# LED.net
KiCad netlist of a schematic drawn in Altium Designer
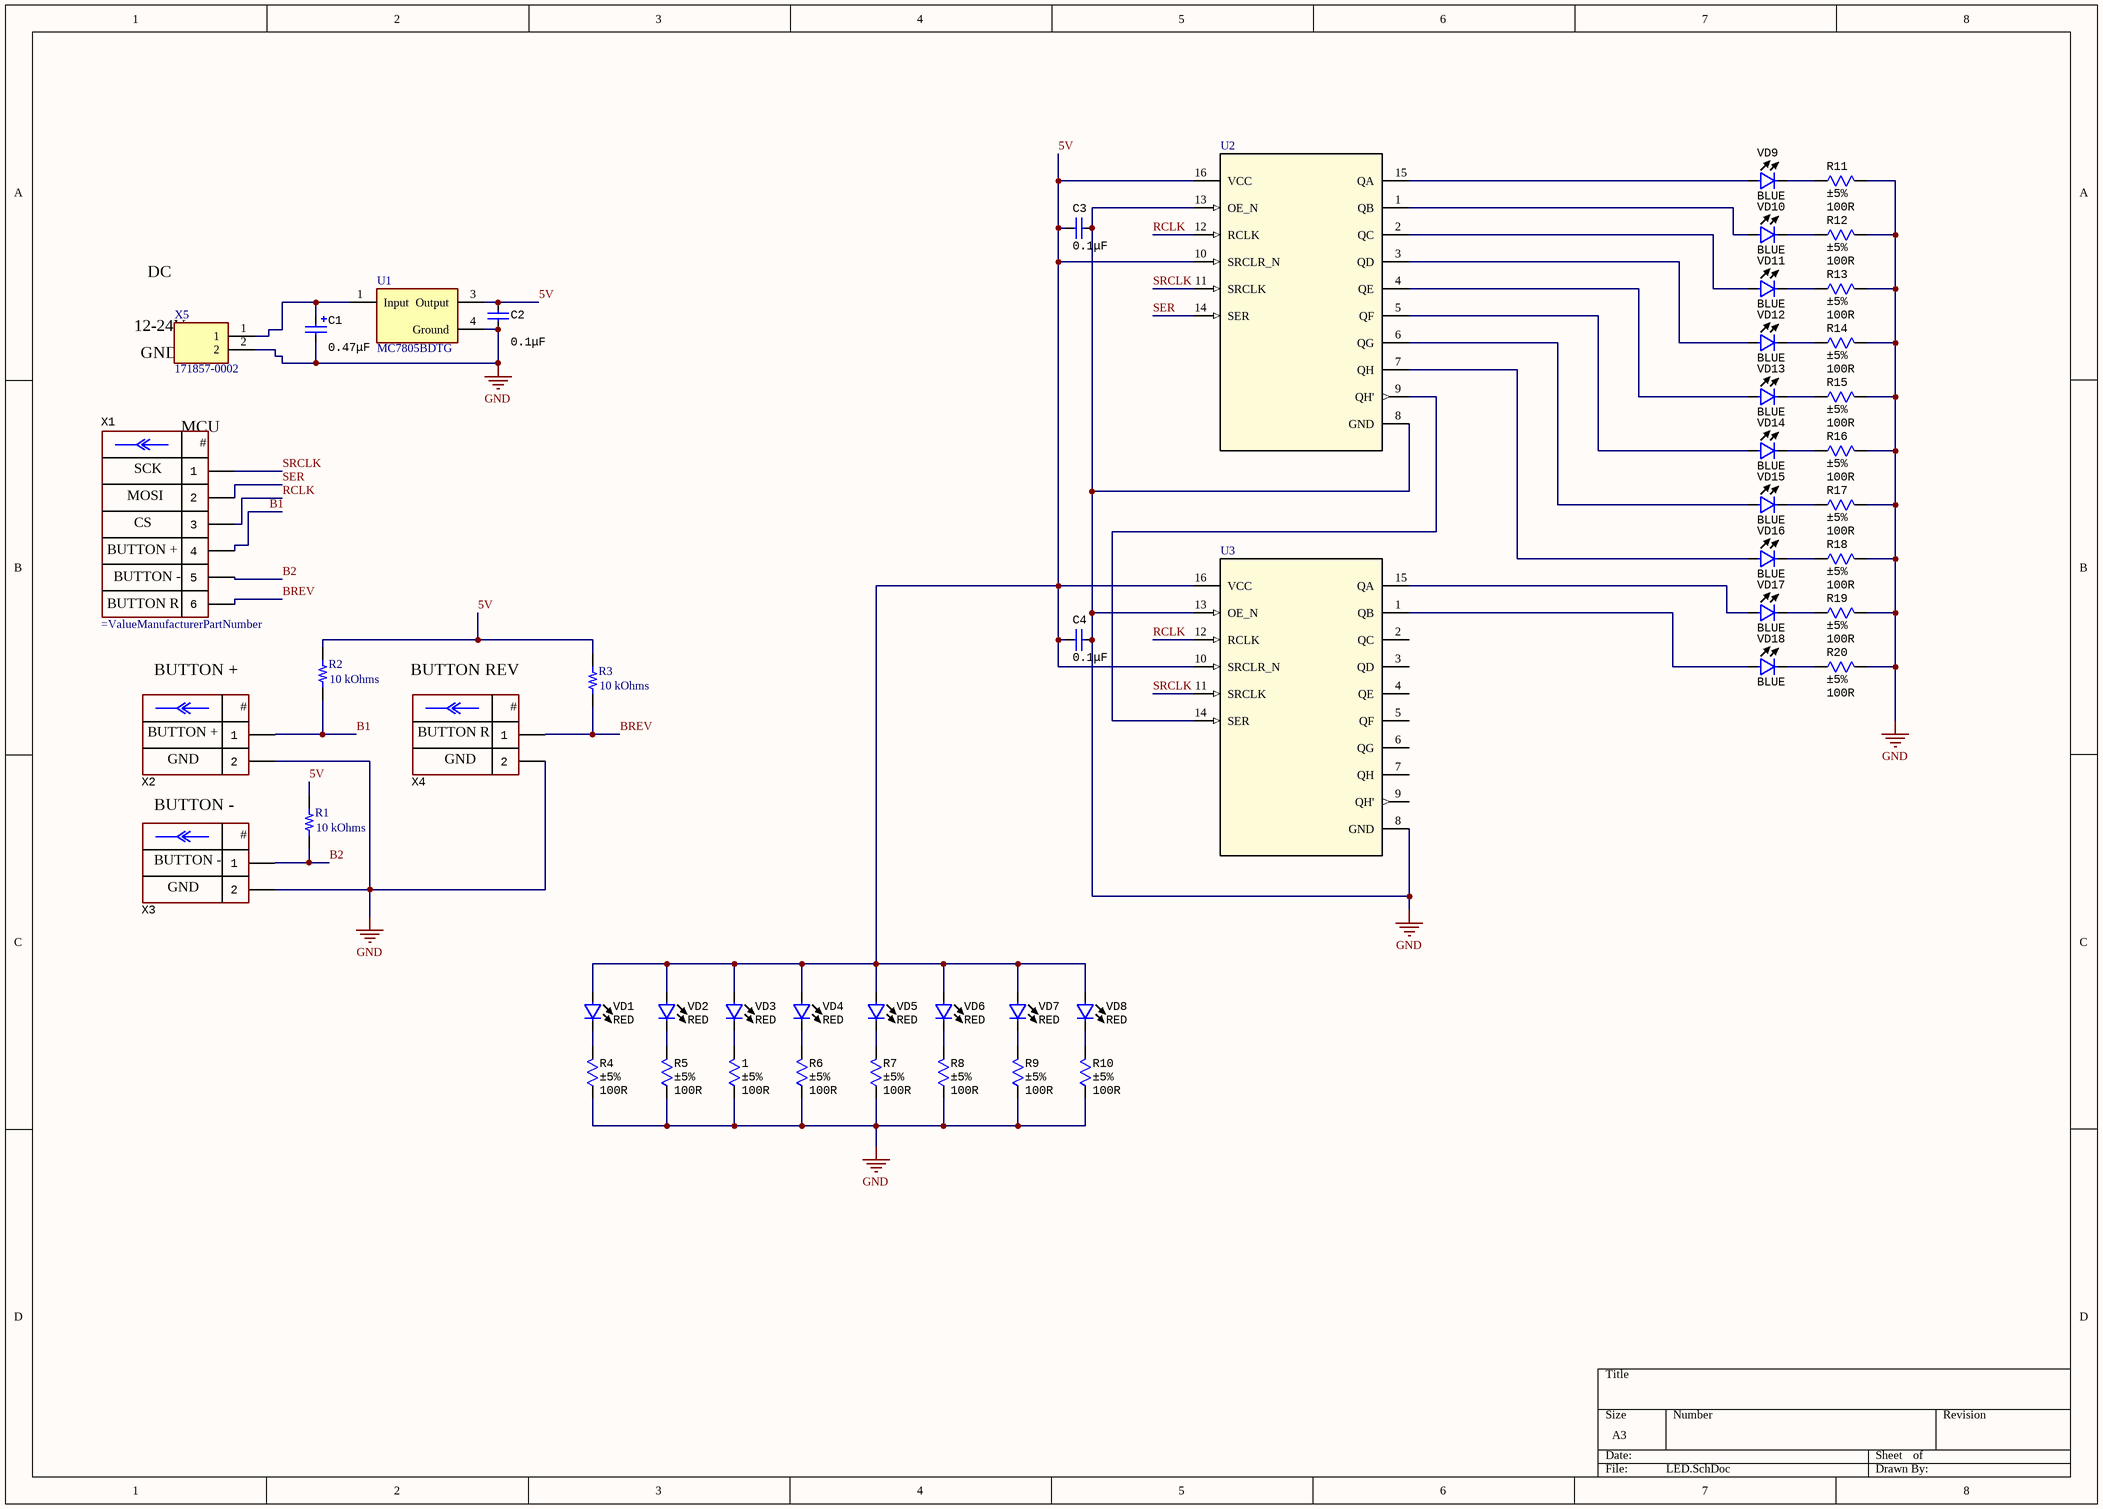
[diagram p0: LED.SchDoc]

(export (version "E")
  (design (tool "Eeschema 10.0.6"))
  (components
    (comp (ref "1")
      (value "100R")
      (footprint "standard-case:RES: 0805")
      (fields
        (field (name "MANUFACTURER") "Yageo")
        (field (name "PARTNUMBER") "RC0201JR-07100RL")
        (field (name "VALUEMANUFACTURERPARTNUMBER") "Resistor film, 100R, ±5%, 0201, 0.05W, -55...+125°C")
        (field (name "TOLERANCE") "±5%")
      )
      (libsource (lib "resistor") (part "Resistor"))
    )
    (comp (ref "C1")
      (value "0.47μF")
      (footprint "standard-case:CAP: TANTAL-A")
      (fields
        (field (name "MANUFACTURER") "AVX")
        (field (name "PARTNUMBER") "F930J107KAAAJ6")
        (field (name "VALUEMANUFACTURERPARTNUMBER") "Tantalum capacitor, 0.47μF, 6.3V, ±10%, 2Ohm, case A (3216), -55...+125°C")
      )
      (libsource (lib "capacitor") (part "Tantal"))
    )
    (comp (ref "C2")
      (value "0.1μF")
      (footprint "standard-case:CAP: 0805")
      (fields
        (field (name "MANUFACTURER") "Yageo")
        (field (name "PARTNUMBER") "CC0201KRX7R7BB103")
        (field (name "VALUEMANUFACTURERPARTNUMBER") "Ceramic capacitor, 0.1μF, X7R, ±10%, 16V, 0201, -55...+125°C")
      )
      (libsource (lib "capacitor") (part "Ceramic"))
    )
    (comp (ref "C3")
      (value "0.1μF")
      (footprint "standard-case:CAP: 0805")
      (fields
        (field (name "MANUFACTURER") "Yageo")
        (field (name "PARTNUMBER") "CC0201KRX7R7BB103")
        (field (name "VALUEMANUFACTURERPARTNUMBER") "Ceramic capacitor, 0.1μF, X7R, ±10%, 16V, 0201, -55...+125°C")
      )
      (libsource (lib "capacitor") (part "Ceramic"))
    )
    (comp (ref "C4")
      (value "0.1μF")
      (footprint "standard-case:CAP: 0805")
      (fields
        (field (name "MANUFACTURER") "Yageo")
        (field (name "PARTNUMBER") "CC0201KRX7R7BB103")
        (field (name "VALUEMANUFACTURERPARTNUMBER") "Ceramic capacitor, 0.1μF, X7R, ±10%, 16V, 0201, -55...+125°C")
      )
      (libsource (lib "capacitor") (part "Ceramic"))
    )
    (comp (ref "R1")
      (value "10 kOhms")
      (footprint "RES 0805_2012")
      (description "RES SMD 10K OHM 0.5% 1/8W 0805")
      (fields (field (name "PART NUMBER") "RT0805DRD0710KL") (field (name "MANUFACTURER") "Yageo"))
      (libsource (lib "Celestial Altium Library - altium_library") (part "Resistor"))
    )
    (comp (ref "R2")
      (value "10 kOhms")
      (footprint "RES 0805_2012")
      (description "RES SMD 10K OHM 0.5% 1/8W 0805")
      (fields (field (name "PART NUMBER") "RT0805DRD0710KL") (field (name "MANUFACTURER") "Yageo"))
      (libsource (lib "Celestial Altium Library - altium_library") (part "Resistor"))
    )
    (comp (ref "R3")
      (value "10 kOhms")
      (footprint "RES 0805_2012")
      (description "RES SMD 10K OHM 0.5% 1/8W 0805")
      (fields (field (name "PART NUMBER") "RT0805DRD0710KL") (field (name "MANUFACTURER") "Yageo"))
      (libsource (lib "Celestial Altium Library - altium_library") (part "Resistor"))
    )
    (comp (ref "R4")
      (value "100R")
      (footprint "standard-case:RES: 0805")
      (fields
        (field (name "MANUFACTURER") "Yageo")
        (field (name "PARTNUMBER") "RC0201JR-07100RL")
        (field (name "VALUEMANUFACTURERPARTNUMBER") "Resistor film, 100R, ±5%, 0201, 0.05W, -55...+125°C")
        (field (name "TOLERANCE") "±5%")
      )
      (libsource (lib "resistor") (part "Resistor"))
    )
    (comp (ref "R5")
      (value "100R")
      (footprint "standard-case:RES: 0805")
      (fields
        (field (name "MANUFACTURER") "Yageo")
        (field (name "PARTNUMBER") "RC0201JR-07100RL")
        (field (name "VALUEMANUFACTURERPARTNUMBER") "Resistor film, 100R, ±5%, 0201, 0.05W, -55...+125°C")
        (field (name "TOLERANCE") "±5%")
      )
      (libsource (lib "resistor") (part "Resistor"))
    )
    (comp (ref "R6")
      (value "100R")
      (footprint "standard-case:RES: 0805")
      (fields
        (field (name "MANUFACTURER") "Yageo")
        (field (name "PARTNUMBER") "RC0201JR-07100RL")
        (field (name "VALUEMANUFACTURERPARTNUMBER") "Resistor film, 100R, ±5%, 0201, 0.05W, -55...+125°C")
        (field (name "TOLERANCE") "±5%")
      )
      (libsource (lib "resistor") (part "Resistor"))
    )
    (comp (ref "R7")
      (value "100R")
      (footprint "standard-case:RES: 0805")
      (fields
        (field (name "MANUFACTURER") "Yageo")
        (field (name "PARTNUMBER") "RC0201JR-07100RL")
        (field (name "VALUEMANUFACTURERPARTNUMBER") "Resistor film, 100R, ±5%, 0201, 0.05W, -55...+125°C")
        (field (name "TOLERANCE") "±5%")
      )
      (libsource (lib "resistor") (part "Resistor"))
    )
    (comp (ref "R8")
      (value "100R")
      (footprint "standard-case:RES: 0805")
      (fields
        (field (name "MANUFACTURER") "Yageo")
        (field (name "PARTNUMBER") "RC0201JR-07100RL")
        (field (name "VALUEMANUFACTURERPARTNUMBER") "Resistor film, 100R, ±5%, 0201, 0.05W, -55...+125°C")
        (field (name "TOLERANCE") "±5%")
      )
      (libsource (lib "resistor") (part "Resistor"))
    )
    (comp (ref "R9")
      (value "100R")
      (footprint "standard-case:RES: 0805")
      (fields
        (field (name "MANUFACTURER") "Yageo")
        (field (name "PARTNUMBER") "RC0201JR-07100RL")
        (field (name "VALUEMANUFACTURERPARTNUMBER") "Resistor film, 100R, ±5%, 0201, 0.05W, -55...+125°C")
        (field (name "TOLERANCE") "±5%")
      )
      (libsource (lib "resistor") (part "Resistor"))
    )
    (comp (ref "R10")
      (value "100R")
      (footprint "standard-case:RES: 0805")
      (fields
        (field (name "MANUFACTURER") "Yageo")
        (field (name "PARTNUMBER") "RC0201JR-07100RL")
        (field (name "VALUEMANUFACTURERPARTNUMBER") "Resistor film, 100R, ±5%, 0201, 0.05W, -55...+125°C")
        (field (name "TOLERANCE") "±5%")
      )
      (libsource (lib "resistor") (part "Resistor"))
    )
    (comp (ref "R11")
      (value "100R")
      (footprint "standard-case:RES: 0805")
      (fields
        (field (name "MANUFACTURER") "Yageo")
        (field (name "PARTNUMBER") "RC0201JR-07100RL")
        (field (name "VALUEMANUFACTURERPARTNUMBER") "Resistor film, 100R, ±5%, 0201, 0.05W, -55...+125°C")
        (field (name "TOLERANCE") "±5%")
      )
      (libsource (lib "resistor") (part "Resistor"))
    )
    (comp (ref "R12")
      (value "100R")
      (footprint "standard-case:RES: 0805")
      (fields
        (field (name "MANUFACTURER") "Yageo")
        (field (name "PARTNUMBER") "RC0201JR-07100RL")
        (field (name "VALUEMANUFACTURERPARTNUMBER") "Resistor film, 100R, ±5%, 0201, 0.05W, -55...+125°C")
        (field (name "TOLERANCE") "±5%")
      )
      (libsource (lib "resistor") (part "Resistor"))
    )
    (comp (ref "R13")
      (value "100R")
      (footprint "standard-case:RES: 0805")
      (fields
        (field (name "MANUFACTURER") "Yageo")
        (field (name "PARTNUMBER") "RC0201JR-07100RL")
        (field (name "VALUEMANUFACTURERPARTNUMBER") "Resistor film, 100R, ±5%, 0201, 0.05W, -55...+125°C")
        (field (name "TOLERANCE") "±5%")
      )
      (libsource (lib "resistor") (part "Resistor"))
    )
    (comp (ref "R14")
      (value "100R")
      (footprint "standard-case:RES: 0805")
      (fields
        (field (name "MANUFACTURER") "Yageo")
        (field (name "PARTNUMBER") "RC0201JR-07100RL")
        (field (name "VALUEMANUFACTURERPARTNUMBER") "Resistor film, 100R, ±5%, 0201, 0.05W, -55...+125°C")
        (field (name "TOLERANCE") "±5%")
      )
      (libsource (lib "resistor") (part "Resistor"))
    )
    (comp (ref "R15")
      (value "100R")
      (footprint "standard-case:RES: 0805")
      (fields
        (field (name "MANUFACTURER") "Yageo")
        (field (name "PARTNUMBER") "RC0201JR-07100RL")
        (field (name "VALUEMANUFACTURERPARTNUMBER") "Resistor film, 100R, ±5%, 0201, 0.05W, -55...+125°C")
        (field (name "TOLERANCE") "±5%")
      )
      (libsource (lib "resistor") (part "Resistor"))
    )
    (comp (ref "R16")
      (value "100R")
      (footprint "standard-case:RES: 0805")
      (fields
        (field (name "MANUFACTURER") "Yageo")
        (field (name "PARTNUMBER") "RC0201JR-07100RL")
        (field (name "VALUEMANUFACTURERPARTNUMBER") "Resistor film, 100R, ±5%, 0201, 0.05W, -55...+125°C")
        (field (name "TOLERANCE") "±5%")
      )
      (libsource (lib "resistor") (part "Resistor"))
    )
    (comp (ref "R17")
      (value "100R")
      (footprint "standard-case:RES: 0805")
      (fields
        (field (name "MANUFACTURER") "Yageo")
        (field (name "PARTNUMBER") "RC0201JR-07100RL")
        (field (name "VALUEMANUFACTURERPARTNUMBER") "Resistor film, 100R, ±5%, 0201, 0.05W, -55...+125°C")
        (field (name "TOLERANCE") "±5%")
      )
      (libsource (lib "resistor") (part "Resistor"))
    )
    (comp (ref "R18")
      (value "100R")
      (footprint "standard-case:RES: 0805")
      (fields
        (field (name "MANUFACTURER") "Yageo")
        (field (name "PARTNUMBER") "RC0201JR-07100RL")
        (field (name "VALUEMANUFACTURERPARTNUMBER") "Resistor film, 100R, ±5%, 0201, 0.05W, -55...+125°C")
        (field (name "TOLERANCE") "±5%")
      )
      (libsource (lib "resistor") (part "Resistor"))
    )
    (comp (ref "R19")
      (value "100R")
      (footprint "standard-case:RES: 0805")
      (fields
        (field (name "MANUFACTURER") "Yageo")
        (field (name "PARTNUMBER") "RC0201JR-07100RL")
        (field (name "VALUEMANUFACTURERPARTNUMBER") "Resistor film, 100R, ±5%, 0201, 0.05W, -55...+125°C")
        (field (name "TOLERANCE") "±5%")
      )
      (libsource (lib "resistor") (part "Resistor"))
    )
    (comp (ref "R20")
      (value "100R")
      (footprint "standard-case:RES: 0805")
      (fields
        (field (name "MANUFACTURER") "Yageo")
        (field (name "PARTNUMBER") "RC0201JR-07100RL")
        (field (name "VALUEMANUFACTURERPARTNUMBER") "Resistor film, 100R, ±5%, 0201, 0.05W, -55...+125°C")
        (field (name "TOLERANCE") "±5%")
      )
      (libsource (lib "resistor") (part "Resistor"))
    )
    (comp (ref "U1")
      (value "IC_ON_Semi_MC7805BDTG_eec")
      (footprint "ON_Semi_CASE_369C_0")
      (description "IC REG LINEAR 5V 1A DPAK-3")
      (fields
        (field (name "MANUFACTURER") "ON Semi")
        (field (name "MOUSER PART NUMBER") "863-MC7805BDTG")
        (field (name "PART NUMBER") "MC7805BDTG")
      )
      (libsource (lib "Integrated_Library1") (part "IC_ON_Semi_MC7805BDTG_eec"))
    )
    (comp (ref "U2")
      (value "~")
      (footprint "D0016A_N")
      (description "No Description Available")
      (fields
        (field (name "PARTNUMBER") "SN74HC595DR")
        (field (name "MANUFACTURER") "Texas Instruments")
        (field (name "COPYRIGHT") "Copyright (C) 2021 Accelerated Designs. All rights reserved")
      )
      (libsource (lib "Shift") (part "SN74HC595D"))
    )
    (comp (ref "U3")
      (value "~")
      (footprint "D0016A_N")
      (description "No Description Available")
      (fields
        (field (name "PARTNUMBER") "SN74HC595DR")
        (field (name "MANUFACTURER") "Texas Instruments")
        (field (name "COPYRIGHT") "Copyright (C) 2021 Accelerated Designs. All rights reserved")
      )
      (libsource (lib "Shift") (part "SN74HC595D"))
    )
    (comp (ref "VD1")
      (value "~")
      (footprint "standard-case:LED: 1206R")
      (fields
        (field (name "VALUEMANUFACTURERPARTNUMBER") "LED, RED, *, *, *, -55...+150°C")
        (field (name "COLOR") "RED")
      )
      (libsource (lib "diode") (part "LED_single"))
    )
    (comp (ref "VD2")
      (value "~")
      (footprint "standard-case:LED: 1206R")
      (fields
        (field (name "VALUEMANUFACTURERPARTNUMBER") "LED, RED, *, *, *, -55...+150°C")
        (field (name "COLOR") "RED")
      )
      (libsource (lib "diode") (part "LED_single"))
    )
    (comp (ref "VD3")
      (value "~")
      (footprint "standard-case:LED: 1206R")
      (fields
        (field (name "VALUEMANUFACTURERPARTNUMBER") "LED, RED, *, *, *, -55...+150°C")
        (field (name "COLOR") "RED")
      )
      (libsource (lib "diode") (part "LED_single"))
    )
    (comp (ref "VD4")
      (value "~")
      (footprint "standard-case:LED: 1206R")
      (fields
        (field (name "VALUEMANUFACTURERPARTNUMBER") "LED, RED, *, *, *, -55...+150°C")
        (field (name "COLOR") "RED")
      )
      (libsource (lib "diode") (part "LED_single"))
    )
    (comp (ref "VD5")
      (value "~")
      (footprint "standard-case:LED: 1206R")
      (fields
        (field (name "VALUEMANUFACTURERPARTNUMBER") "LED, RED, *, *, *, -55...+150°C")
        (field (name "COLOR") "RED")
      )
      (libsource (lib "diode") (part "LED_single"))
    )
    (comp (ref "VD6")
      (value "~")
      (footprint "standard-case:LED: 1206R")
      (fields
        (field (name "VALUEMANUFACTURERPARTNUMBER") "LED, RED, *, *, *, -55...+150°C")
        (field (name "COLOR") "RED")
      )
      (libsource (lib "diode") (part "LED_single"))
    )
    (comp (ref "VD7")
      (value "~")
      (footprint "standard-case:LED: 1206R")
      (fields
        (field (name "VALUEMANUFACTURERPARTNUMBER") "LED, RED, *, *, *, -55...+150°C")
        (field (name "COLOR") "RED")
      )
      (libsource (lib "diode") (part "LED_single"))
    )
    (comp (ref "VD8")
      (value "~")
      (footprint "standard-case:LED: 1206R")
      (fields
        (field (name "VALUEMANUFACTURERPARTNUMBER") "LED, RED, *, *, *, -55...+150°C")
        (field (name "COLOR") "RED")
      )
      (libsource (lib "diode") (part "LED_single"))
    )
    (comp (ref "VD9")
      (value "~")
      (footprint "standard-case:LED: 1206B")
      (fields
        (field (name "VALUEMANUFACTURERPARTNUMBER") "LED, BLUE, *, *, *, -55...+150°C")
        (field (name "COLOR") "BLUE")
      )
      (libsource (lib "diode") (part "LED_single"))
    )
    (comp (ref "VD10")
      (value "~")
      (footprint "standard-case:LED: 1206B")
      (fields
        (field (name "VALUEMANUFACTURERPARTNUMBER") "LED, BLUE, *, *, *, -55...+150°C")
        (field (name "COLOR") "BLUE")
      )
      (libsource (lib "diode") (part "LED_single"))
    )
    (comp (ref "VD11")
      (value "~")
      (footprint "standard-case:LED: 1206B")
      (fields
        (field (name "VALUEMANUFACTURERPARTNUMBER") "LED, BLUE, *, *, *, -55...+150°C")
        (field (name "COLOR") "BLUE")
      )
      (libsource (lib "diode") (part "LED_single"))
    )
    (comp (ref "VD12")
      (value "~")
      (footprint "standard-case:LED: 1206B")
      (fields
        (field (name "VALUEMANUFACTURERPARTNUMBER") "LED, BLUE, *, *, *, -55...+150°C")
        (field (name "COLOR") "BLUE")
      )
      (libsource (lib "diode") (part "LED_single"))
    )
    (comp (ref "VD13")
      (value "~")
      (footprint "standard-case:LED: 1206B")
      (fields
        (field (name "VALUEMANUFACTURERPARTNUMBER") "LED, BLUE, *, *, *, -55...+150°C")
        (field (name "COLOR") "BLUE")
      )
      (libsource (lib "diode") (part "LED_single"))
    )
    (comp (ref "VD14")
      (value "~")
      (footprint "standard-case:LED: 1206B")
      (fields
        (field (name "VALUEMANUFACTURERPARTNUMBER") "LED, BLUE, *, *, *, -55...+150°C")
        (field (name "COLOR") "BLUE")
      )
      (libsource (lib "diode") (part "LED_single"))
    )
    (comp (ref "VD15")
      (value "~")
      (footprint "standard-case:LED: 1206B")
      (fields
        (field (name "VALUEMANUFACTURERPARTNUMBER") "LED, BLUE, *, *, *, -55...+150°C")
        (field (name "COLOR") "BLUE")
      )
      (libsource (lib "diode") (part "LED_single"))
    )
    (comp (ref "VD16")
      (value "~")
      (footprint "standard-case:LED: 1206B")
      (fields
        (field (name "VALUEMANUFACTURERPARTNUMBER") "LED, BLUE, *, *, *, -55...+150°C")
        (field (name "COLOR") "BLUE")
      )
      (libsource (lib "diode") (part "LED_single"))
    )
    (comp (ref "VD17")
      (value "~")
      (footprint "standard-case:LED: 1206B")
      (fields
        (field (name "VALUEMANUFACTURERPARTNUMBER") "LED, BLUE, *, *, *, -55...+150°C")
        (field (name "COLOR") "BLUE")
      )
      (libsource (lib "diode") (part "LED_single"))
    )
    (comp (ref "VD18")
      (value "~")
      (footprint "standard-case:LED: 1206B")
      (fields
        (field (name "VALUEMANUFACTURERPARTNUMBER") "LED, BLUE, *, *, *, -55...+150°C")
        (field (name "COLOR") "BLUE")
      )
      (libsource (lib "diode") (part "LED_single"))
    )
    (comp (ref "X1")
      (value "~")
      (footprint "CON: CWF-6R")
      (fields
        (field (name "MANUFACTURER") "Connfly")
        (field (name "VALUEMANUFACTURERPARTNUMBER") "Connector, 6pin, 2.54mm, 250VAC, 3A")
        (field (name "PARTNUMBER") "CWF-6R")
      )
      (libsource (lib "connector") (part "CWF-6"))
    )
    (comp (ref "X2")
      (value "~")
      (footprint "MW-2MR")
      (fields
        (field (name "MANUFACTURER") "Connfly")
        (field (name "VALUEMANUFACTURERPARTNUMBER") "Connector, 2pin, 2.54mm, 250VAC, 3A")
        (field (name "PARTNUMBER") "CWF-2R")
      )
      (libsource (lib "connector") (part "CWF-2"))
    )
    (comp (ref "X3")
      (value "~")
      (footprint "MW-2MR")
      (fields
        (field (name "MANUFACTURER") "Connfly")
        (field (name "VALUEMANUFACTURERPARTNUMBER") "Connector, 2pin, 2.54mm, 250VAC, 3A")
        (field (name "PARTNUMBER") "CWF-2R")
      )
      (libsource (lib "connector") (part "CWF-2"))
    )
    (comp (ref "X4")
      (value "~")
      (footprint "MW-2MR")
      (fields
        (field (name "MANUFACTURER") "Connfly")
        (field (name "VALUEMANUFACTURERPARTNUMBER") "Connector, 2pin, 2.54mm, 250VAC, 3A")
        (field (name "PARTNUMBER") "CWF-2R")
      )
      (libsource (lib "connector") (part "CWF-2"))
    )
    (comp (ref "X5")
      (value "171857-0002")
      (footprint "SamacSys:171857-0002")
      (description "Connector")
      (fields (field (name "MOUSER PART NUMBER") "538-171857-0002"))
      (libsource (lib "*") (part "171857-0002"))
    )
  )
  (nets
    (net (code "1") (name "/5V") (class "Default")
      (node (ref "C2") (pin "1") (pinfunction "1_1") (pintype "passive"))
      (node (ref "C3") (pin "1") (pinfunction "1_1") (pintype "passive"))
      (node (ref "C4") (pin "1") (pinfunction "1_1") (pintype "passive"))
      (node (ref "R1") (pin "2") (pinfunction "2_2") (pintype "passive"))
      (node (ref "R2") (pin "2") (pinfunction "2_2") (pintype "passive"))
      (node (ref "R3") (pin "2") (pinfunction "2_2") (pintype "passive"))
      (node (ref "U1") (pin "3") (pinfunction "Output_3") (pintype "passive"))
      (node (ref "U2") (pin "10") (pinfunction "SRCLR_N_10") (pintype "input"))
      (node (ref "U2") (pin "16") (pinfunction "VCC_16") (pintype "power_in"))
      (node (ref "U3") (pin "10") (pinfunction "SRCLR_N_10") (pintype "input"))
      (node (ref "U3") (pin "16") (pinfunction "VCC_16") (pintype "power_in"))
      (node (ref "VD1") (pin "1") (pinfunction "1_1") (pintype "passive"))
      (node (ref "VD2") (pin "1") (pinfunction "1_1") (pintype "passive"))
      (node (ref "VD3") (pin "1") (pinfunction "1_1") (pintype "passive"))
      (node (ref "VD4") (pin "1") (pinfunction "1_1") (pintype "passive"))
      (node (ref "VD5") (pin "1") (pinfunction "1_1") (pintype "passive"))
      (node (ref "VD6") (pin "1") (pinfunction "1_1") (pintype "passive"))
      (node (ref "VD7") (pin "1") (pinfunction "1_1") (pintype "passive"))
      (node (ref "VD8") (pin "1") (pinfunction "1_1") (pintype "passive"))
    )
    (net (code "2") (name "/B1") (class "Default")
      (node (ref "R2") (pin "1") (pinfunction "1_1") (pintype "passive"))
      (node (ref "X1") (pin "4") (pinfunction "4_4") (pintype "power_in"))
      (node (ref "X2") (pin "1") (pinfunction "1_1") (pintype "passive"))
    )
    (net (code "3") (name "/B2") (class "Default")
      (node (ref "R1") (pin "1") (pinfunction "1_1") (pintype "passive"))
      (node (ref "X1") (pin "5") (pinfunction "5_5") (pintype "power_in"))
      (node (ref "X3") (pin "1") (pinfunction "1_1") (pintype "passive"))
    )
    (net (code "4") (name "/BREV") (class "Default")
      (node (ref "R3") (pin "1") (pinfunction "1_1") (pintype "passive"))
      (node (ref "X1") (pin "6") (pinfunction "6_6") (pintype "power_in"))
      (node (ref "X4") (pin "1") (pinfunction "1_1") (pintype "passive"))
    )
    (net (code "5") (name "/RCLK") (class "Default")
      (node (ref "U2") (pin "12") (pinfunction "RCLK_12") (pintype "input"))
      (node (ref "U3") (pin "12") (pinfunction "RCLK_12") (pintype "input"))
      (node (ref "X1") (pin "3") (pinfunction "3_3") (pintype "power_in"))
    )
    (net (code "6") (name "/SER") (class "Default")
      (node (ref "U2") (pin "14") (pinfunction "SER_14") (pintype "input"))
      (node (ref "X1") (pin "2") (pinfunction "2_2") (pintype "passive"))
    )
    (net (code "7") (name "/SRCLK") (class "Default")
      (node (ref "U2") (pin "11") (pinfunction "SRCLK_11") (pintype "input"))
      (node (ref "U3") (pin "11") (pinfunction "SRCLK_11") (pintype "input"))
      (node (ref "X1") (pin "1") (pinfunction "1_1") (pintype "passive"))
    )
    (net (code "8") (name "GND") (class "Default")
      (node (ref "1") (pin "1") (pinfunction "1_1") (pintype "passive"))
      (node (ref "C1") (pin "2") (pinfunction "2_2") (pintype "passive"))
      (node (ref "C2") (pin "2") (pinfunction "2_2") (pintype "passive"))
      (node (ref "C3") (pin "2") (pinfunction "2_2") (pintype "passive"))
      (node (ref "C4") (pin "2") (pinfunction "2_2") (pintype "passive"))
      (node (ref "R10") (pin "1") (pinfunction "1_1") (pintype "passive"))
      (node (ref "R11") (pin "2") (pinfunction "2_2") (pintype "passive"))
      (node (ref "R12") (pin "2") (pinfunction "2_2") (pintype "passive"))
      (node (ref "R13") (pin "2") (pinfunction "2_2") (pintype "passive"))
      (node (ref "R14") (pin "2") (pinfunction "2_2") (pintype "passive"))
      (node (ref "R15") (pin "2") (pinfunction "2_2") (pintype "passive"))
      (node (ref "R16") (pin "2") (pinfunction "2_2") (pintype "passive"))
      (node (ref "R17") (pin "2") (pinfunction "2_2") (pintype "passive"))
      (node (ref "R18") (pin "2") (pinfunction "2_2") (pintype "passive"))
      (node (ref "R19") (pin "2") (pinfunction "2_2") (pintype "passive"))
      (node (ref "R20") (pin "2") (pinfunction "2_2") (pintype "passive"))
      (node (ref "R4") (pin "1") (pinfunction "1_1") (pintype "passive"))
      (node (ref "R5") (pin "1") (pinfunction "1_1") (pintype "passive"))
      (node (ref "R6") (pin "1") (pinfunction "1_1") (pintype "passive"))
      (node (ref "R7") (pin "1") (pinfunction "1_1") (pintype "passive"))
      (node (ref "R8") (pin "1") (pinfunction "1_1") (pintype "passive"))
      (node (ref "R9") (pin "1") (pinfunction "1_1") (pintype "passive"))
      (node (ref "U1") (pin "4") (pinfunction "Ground_4") (pintype "passive"))
      (node (ref "U2") (pin "13") (pinfunction "OE_N_13") (pintype "input"))
      (node (ref "U2") (pin "8") (pinfunction "GND_8") (pintype "power_in"))
      (node (ref "U3") (pin "13") (pinfunction "OE_N_13") (pintype "input"))
      (node (ref "U3") (pin "8") (pinfunction "GND_8") (pintype "power_in"))
      (node (ref "X2") (pin "2") (pinfunction "2_2") (pintype "passive"))
      (node (ref "X3") (pin "2") (pinfunction "2_2") (pintype "passive"))
      (node (ref "X4") (pin "2") (pinfunction "2_2") (pintype "passive"))
      (node (ref "X5") (pin "2") (pinfunction "2_2") (pintype "passive"))
    )
    (net (code "9") (name "Net-(1-Pad2)") (class "Default")
      (node (ref "1") (pin "2") (pinfunction "2_2") (pintype "passive"))
      (node (ref "VD3") (pin "2") (pinfunction "2_2") (pintype "passive"))
    )
    (net (code "10") (name "Net-(R4-Pad2)") (class "Default")
      (node (ref "R4") (pin "2") (pinfunction "2_2") (pintype "passive"))
      (node (ref "VD1") (pin "2") (pinfunction "2_2") (pintype "passive"))
    )
    (net (code "11") (name "Net-(R5-Pad2)") (class "Default")
      (node (ref "R5") (pin "2") (pinfunction "2_2") (pintype "passive"))
      (node (ref "VD2") (pin "2") (pinfunction "2_2") (pintype "passive"))
    )
    (net (code "12") (name "Net-(R6-Pad2)") (class "Default")
      (node (ref "R6") (pin "2") (pinfunction "2_2") (pintype "passive"))
      (node (ref "VD4") (pin "2") (pinfunction "2_2") (pintype "passive"))
    )
    (net (code "13") (name "Net-(R7-Pad2)") (class "Default")
      (node (ref "R7") (pin "2") (pinfunction "2_2") (pintype "passive"))
      (node (ref "VD5") (pin "2") (pinfunction "2_2") (pintype "passive"))
    )
    (net (code "14") (name "Net-(R8-Pad2)") (class "Default")
      (node (ref "R8") (pin "2") (pinfunction "2_2") (pintype "passive"))
      (node (ref "VD6") (pin "2") (pinfunction "2_2") (pintype "passive"))
    )
    (net (code "15") (name "Net-(R9-Pad2)") (class "Default")
      (node (ref "R9") (pin "2") (pinfunction "2_2") (pintype "passive"))
      (node (ref "VD7") (pin "2") (pinfunction "2_2") (pintype "passive"))
    )
    (net (code "16") (name "Net-(R10-Pad2)") (class "Default")
      (node (ref "R10") (pin "2") (pinfunction "2_2") (pintype "passive"))
      (node (ref "VD8") (pin "2") (pinfunction "2_2") (pintype "passive"))
    )
    (net (code "17") (name "Net-(R11-Pad1)") (class "Default")
      (node (ref "R11") (pin "1") (pinfunction "1_1") (pintype "passive"))
      (node (ref "VD9") (pin "2") (pinfunction "2_2") (pintype "passive"))
    )
    (net (code "18") (name "Net-(R12-Pad1)") (class "Default")
      (node (ref "R12") (pin "1") (pinfunction "1_1") (pintype "passive"))
      (node (ref "VD10") (pin "2") (pinfunction "2_2") (pintype "passive"))
    )
    (net (code "19") (name "Net-(R13-Pad1)") (class "Default")
      (node (ref "R13") (pin "1") (pinfunction "1_1") (pintype "passive"))
      (node (ref "VD11") (pin "2") (pinfunction "2_2") (pintype "passive"))
    )
    (net (code "20") (name "Net-(R14-Pad1)") (class "Default")
      (node (ref "R14") (pin "1") (pinfunction "1_1") (pintype "passive"))
      (node (ref "VD12") (pin "2") (pinfunction "2_2") (pintype "passive"))
    )
    (net (code "21") (name "Net-(R15-Pad1)") (class "Default")
      (node (ref "R15") (pin "1") (pinfunction "1_1") (pintype "passive"))
      (node (ref "VD13") (pin "2") (pinfunction "2_2") (pintype "passive"))
    )
    (net (code "22") (name "Net-(R16-Pad1)") (class "Default")
      (node (ref "R16") (pin "1") (pinfunction "1_1") (pintype "passive"))
      (node (ref "VD14") (pin "2") (pinfunction "2_2") (pintype "passive"))
    )
    (net (code "23") (name "Net-(R17-Pad1)") (class "Default")
      (node (ref "R17") (pin "1") (pinfunction "1_1") (pintype "passive"))
      (node (ref "VD15") (pin "2") (pinfunction "2_2") (pintype "passive"))
    )
    (net (code "24") (name "Net-(R18-Pad1)") (class "Default")
      (node (ref "R18") (pin "1") (pinfunction "1_1") (pintype "passive"))
      (node (ref "VD16") (pin "2") (pinfunction "2_2") (pintype "passive"))
    )
    (net (code "25") (name "Net-(R19-Pad1)") (class "Default")
      (node (ref "R19") (pin "1") (pinfunction "1_1") (pintype "passive"))
      (node (ref "VD17") (pin "2") (pinfunction "2_2") (pintype "passive"))
    )
    (net (code "26") (name "Net-(R20-Pad1)") (class "Default")
      (node (ref "R20") (pin "1") (pinfunction "1_1") (pintype "passive"))
      (node (ref "VD18") (pin "2") (pinfunction "2_2") (pintype "passive"))
    )
    (net (code "27") (name "Net-(U1-Input)") (class "Default")
      (node (ref "C1") (pin "1") (pinfunction "1_1") (pintype "passive"))
      (node (ref "U1") (pin "1") (pinfunction "Input_1") (pintype "passive"))
      (node (ref "X5") (pin "1") (pinfunction "1_1") (pintype "passive"))
    )
    (net (code "28") (name "Net-(U2-QA)") (class "Default")
      (node (ref "U2") (pin "15") (pinfunction "QA_15") (pintype "tri_state"))
      (node (ref "VD9") (pin "1") (pinfunction "1_1") (pintype "passive"))
    )
    (net (code "29") (name "Net-(U2-QB)") (class "Default")
      (node (ref "U2") (pin "1") (pinfunction "QB_1") (pintype "tri_state"))
      (node (ref "VD10") (pin "1") (pinfunction "1_1") (pintype "passive"))
    )
    (net (code "30") (name "Net-(U2-QC)") (class "Default")
      (node (ref "U2") (pin "2") (pinfunction "QC_2") (pintype "tri_state"))
      (node (ref "VD11") (pin "1") (pinfunction "1_1") (pintype "passive"))
    )
    (net (code "31") (name "Net-(U2-QD)") (class "Default")
      (node (ref "U2") (pin "3") (pinfunction "QD_3") (pintype "tri_state"))
      (node (ref "VD12") (pin "1") (pinfunction "1_1") (pintype "passive"))
    )
    (net (code "32") (name "Net-(U2-QE)") (class "Default")
      (node (ref "U2") (pin "4") (pinfunction "QE_4") (pintype "tri_state"))
      (node (ref "VD13") (pin "1") (pinfunction "1_1") (pintype "passive"))
    )
    (net (code "33") (name "Net-(U2-QF)") (class "Default")
      (node (ref "U2") (pin "5") (pinfunction "QF_5") (pintype "tri_state"))
      (node (ref "VD14") (pin "1") (pinfunction "1_1") (pintype "passive"))
    )
    (net (code "34") (name "Net-(U2-QG)") (class "Default")
      (node (ref "U2") (pin "6") (pinfunction "QG_6") (pintype "tri_state"))
      (node (ref "VD15") (pin "1") (pinfunction "1_1") (pintype "passive"))
    )
    (net (code "35") (name "Net-(U2-QH')") (class "Default")
      (node (ref "U2") (pin "9") (pinfunction "QH'_9") (pintype "output"))
      (node (ref "U3") (pin "14") (pinfunction "SER_14") (pintype "input"))
    )
    (net (code "36") (name "Net-(U2-QH)") (class "Default")
      (node (ref "U2") (pin "7") (pinfunction "QH_7") (pintype "tri_state"))
      (node (ref "VD16") (pin "1") (pinfunction "1_1") (pintype "passive"))
    )
    (net (code "37") (name "Net-(U3-QA)") (class "Default")
      (node (ref "U3") (pin "15") (pinfunction "QA_15") (pintype "tri_state"))
      (node (ref "VD17") (pin "1") (pinfunction "1_1") (pintype "passive"))
    )
    (net (code "38") (name "Net-(U3-QB)") (class "Default")
      (node (ref "U3") (pin "1") (pinfunction "QB_1") (pintype "tri_state"))
      (node (ref "VD18") (pin "1") (pinfunction "1_1") (pintype "passive"))
    )
    (net (code "39") (name "unconnected-(U3-QC-Pad2)") (class "Default")
      (node (ref "U3") (pin "2") (pinfunction "QC_2") (pintype "tri_state"))
    )
    (net (code "40") (name "unconnected-(U3-QD-Pad3)") (class "Default")
      (node (ref "U3") (pin "3") (pinfunction "QD_3") (pintype "tri_state"))
    )
    (net (code "41") (name "unconnected-(U3-QE-Pad4)") (class "Default")
      (node (ref "U3") (pin "4") (pinfunction "QE_4") (pintype "tri_state"))
    )
    (net (code "42") (name "unconnected-(U3-QF-Pad5)") (class "Default")
      (node (ref "U3") (pin "5") (pinfunction "QF_5") (pintype "tri_state"))
    )
    (net (code "43") (name "unconnected-(U3-QG-Pad6)") (class "Default")
      (node (ref "U3") (pin "6") (pinfunction "QG_6") (pintype "tri_state"))
    )
    (net (code "44") (name "unconnected-(U3-QH'-Pad9)") (class "Default")
      (node (ref "U3") (pin "9") (pinfunction "QH'_9") (pintype "output"))
    )
    (net (code "45") (name "unconnected-(U3-QH-Pad7)") (class "Default")
      (node (ref "U3") (pin "7") (pinfunction "QH_7") (pintype "tri_state"))
    )
  )
)
